# Flash.net
KiCad netlist of a schematic drawn in Altium Designer
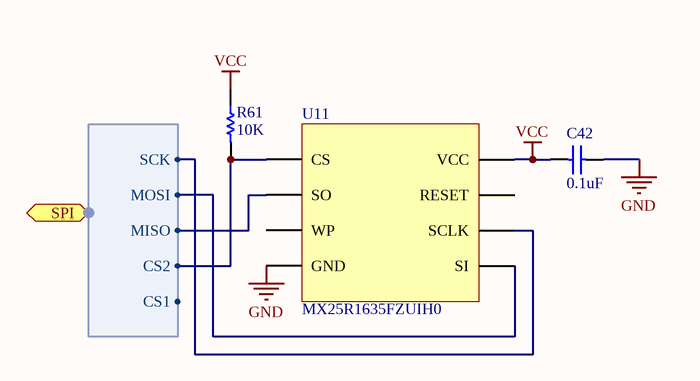
[diagram p0: Flash.SchDoc]

(export (version "E")
  (design (tool "Eeschema 10.0.6"))
  (components
    (comp (ref "C42")
      (value "0.1uF")
      (footprint "C0402[1005X55]")
      (description "0.1uF 6.3V 10% 0402 (1005 Metric)")
      (fields (field (name "PARTNUMBER") "GRM155R70J104KA01D") (field (name "MANUFACTURER") "Murata"))
      (libsource (lib "Capacitors") (part "CAP_0.1uF_6.3V_0402_10%"))
    )
    (comp (ref "R61")
      (value "10K")
      (footprint "R0402[1005]")
      (description "10K 0.063W 1% 0402 (1005 Metric)")
      (fields (field (name "MANUFACTURER") "KOA Speer") (field (name "PARTNUMBER") "RK73H1ETTP1002F"))
      (libsource (lib "Resistors") (part "RES_10K_0402_1%"))
    )
    (comp (ref "U11")
      (value "MX25R1635FZUIH0")
      (footprint "USON-8")
      (fields (field (name "MANUFACTURER") "Macronix"))
      (libsource (lib "ICs") (part "MX25R1635FZUIH0"))
    )
  )
  (nets
    (net (code "2") (name "/CS2") (class "Default")
      (node (ref "R61") (pin "1") (pinfunction "1_1") (pintype "passive"))
      (node (ref "U11") (pin "1") (pinfunction "CS_1") (pintype "passive"))
    )
    (net (code "3") (name "/MISO") (class "Default")
      (node (ref "U11") (pin "2") (pinfunction "SO_2") (pintype "passive"))
    )
    (net (code "4") (name "/MOSI") (class "Default")
      (node (ref "U11") (pin "5") (pinfunction "SI_5") (pintype "power_in"))
    )
    (net (code "5") (name "/SCK") (class "Default")
      (node (ref "U11") (pin "6") (pinfunction "SCLK_6") (pintype "passive"))
    )
    (net (code "7") (name "GND") (class "Default")
      (node (ref "C42") (pin "2") (pinfunction "2_2") (pintype "passive"))
      (node (ref "U11") (pin "4") (pinfunction "GND_4") (pintype "passive"))
    )
    (net (code "8") (name "VCC") (class "Default")
      (node (ref "C42") (pin "1") (pinfunction "1_1") (pintype "passive"))
      (node (ref "R61") (pin "2") (pinfunction "2_2") (pintype "passive"))
      (node (ref "U11") (pin "8") (pinfunction "VCC_8") (pintype "passive"))
    )
    (net (code "9") (name "unconnected-(U11-RESET-Pad7)") (class "Default")
      (node (ref "U11") (pin "7") (pinfunction "RESET_7") (pintype "passive"))
    )
    (net (code "10") (name "unconnected-(U11-WP-Pad3)") (class "Default")
      (node (ref "U11") (pin "3") (pinfunction "WP_3") (pintype "passive"))
    )
  )
)
